# lasertag.net
KiCad netlist of a schematic drawn in EAGLE
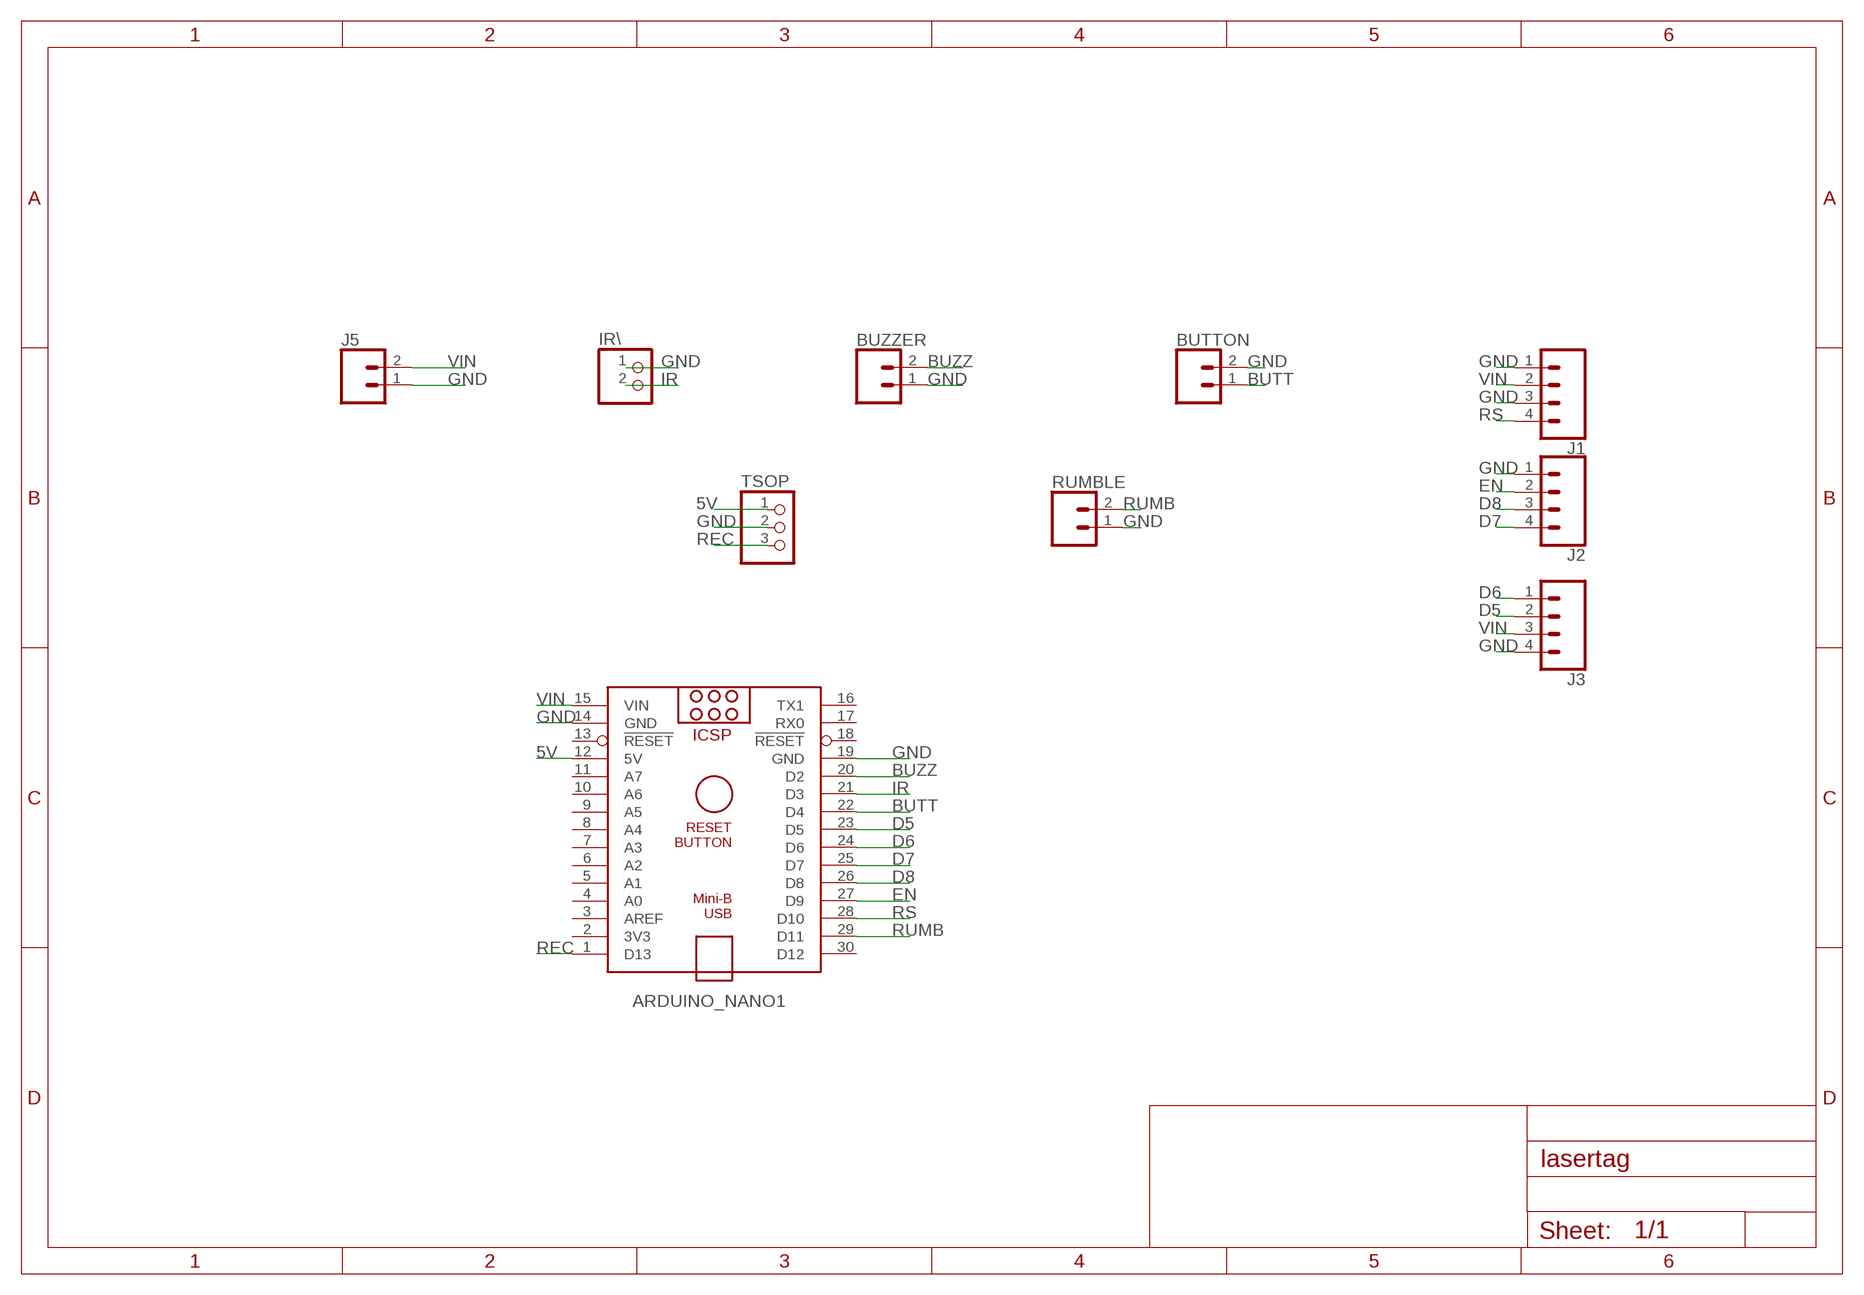
[diagram p0: schematic, sheet 1]

(export (version "E")
  (design (tool "Eeschema 10.0.6"))
  (components
    (comp (ref "ARDUINO_NANO1")
      (value "ARDUINO_NANO")
      (footprint "eagle-import:ARDUINO_NANO")
      (libsource (lib "eagle-import") (part "ARDUINO_NANO"))
    )
    (comp (ref "BUTTON")
      (value "CONN_02")
      (footprint "eagle-import:1X02")
      (libsource (lib "eagle-import") (part "CONN_02"))
    )
    (comp (ref "BUZZER")
      (value "CONN_02")
      (footprint "eagle-import:1X02")
      (libsource (lib "eagle-import") (part "CONN_02"))
    )
    (comp (ref "IR\\")
      (value "PINHD-1X2")
      (footprint "eagle-import:1X02")
      (libsource (lib "eagle-import") (part "PINHD-1X2"))
    )
    (comp (ref "J1")
      (value "CONN_04JST-PTH-VERT")
      (footprint "eagle-import:JST-4-PTH-VERT")
      (libsource (lib "eagle-import") (part "CONN_04JST-PTH-VERT"))
    )
    (comp (ref "J2")
      (value "CONN_04JST-PTH-VERT")
      (footprint "eagle-import:JST-4-PTH-VERT")
      (libsource (lib "eagle-import") (part "CONN_04JST-PTH-VERT"))
    )
    (comp (ref "J3")
      (value "CONN_04JST-PTH-VERT")
      (footprint "eagle-import:JST-4-PTH-VERT")
      (libsource (lib "eagle-import") (part "CONN_04JST-PTH-VERT"))
    )
    (comp (ref "J5")
      (value "CONN_02JST-PTH-VERT")
      (footprint "eagle-import:JST-2-PTH-VERT")
      (libsource (lib "eagle-import") (part "CONN_02JST-PTH-VERT"))
    )
    (comp (ref "RUMBLE")
      (value "CONN_02")
      (footprint "eagle-import:1X02")
      (libsource (lib "eagle-import") (part "CONN_02"))
    )
    (comp (ref "TSOP")
      (value "PINHD-1X3")
      (footprint "eagle-import:1X03")
      (libsource (lib "eagle-import") (part "PINHD-1X3"))
    )
  )
  (nets
    (net (code "1") (name "/5V") (class "Default")
      (node (ref "ARDUINO_NANO1") (pin "12") (pinfunction "5V_12") (pintype "power_in"))
      (node (ref "TSOP") (pin "1") (pinfunction "1_1") (pintype "passive"))
    )
    (net (code "2") (name "/BUTT") (class "Default")
      (node (ref "ARDUINO_NANO1") (pin "22") (pinfunction "D4_22") (pintype "bidirectional"))
      (node (ref "BUTTON") (pin "1") (pinfunction "1_1") (pintype "passive"))
    )
    (net (code "3") (name "/BUZZ") (class "Default")
      (node (ref "ARDUINO_NANO1") (pin "20") (pinfunction "D2_20") (pintype "bidirectional"))
      (node (ref "BUZZER") (pin "2") (pinfunction "2_2") (pintype "passive"))
    )
    (net (code "4") (name "/D5") (class "Default")
      (node (ref "ARDUINO_NANO1") (pin "23") (pinfunction "D5_23") (pintype "bidirectional"))
      (node (ref "J3") (pin "2") (pinfunction "2_2") (pintype "passive"))
    )
    (net (code "5") (name "/D6") (class "Default")
      (node (ref "ARDUINO_NANO1") (pin "24") (pinfunction "D6_24") (pintype "bidirectional"))
      (node (ref "J3") (pin "1") (pinfunction "1_1") (pintype "passive"))
    )
    (net (code "6") (name "/D7") (class "Default")
      (node (ref "ARDUINO_NANO1") (pin "25") (pinfunction "D7_25") (pintype "bidirectional"))
      (node (ref "J2") (pin "4") (pinfunction "4_4") (pintype "passive"))
    )
    (net (code "7") (name "/D8") (class "Default")
      (node (ref "ARDUINO_NANO1") (pin "26") (pinfunction "D8_26") (pintype "bidirectional"))
      (node (ref "J2") (pin "3") (pinfunction "3_3") (pintype "passive"))
    )
    (net (code "8") (name "/EN") (class "Default")
      (node (ref "ARDUINO_NANO1") (pin "27") (pinfunction "D9_27") (pintype "bidirectional"))
      (node (ref "J2") (pin "2") (pinfunction "2_2") (pintype "passive"))
    )
    (net (code "9") (name "/GND") (class "Default")
      (node (ref "ARDUINO_NANO1") (pin "14") (pinfunction "GND_14") (pintype "power_in"))
      (node (ref "ARDUINO_NANO1") (pin "19") (pinfunction "GND_19") (pintype "power_in"))
      (node (ref "BUTTON") (pin "2") (pinfunction "2_2") (pintype "passive"))
      (node (ref "BUZZER") (pin "1") (pinfunction "1_1") (pintype "passive"))
      (node (ref "IR\\") (pin "1") (pinfunction "1_1") (pintype "passive"))
      (node (ref "J1") (pin "1") (pinfunction "1_1") (pintype "passive"))
      (node (ref "J1") (pin "3") (pinfunction "3_3") (pintype "passive"))
      (node (ref "J2") (pin "1") (pinfunction "1_1") (pintype "passive"))
      (node (ref "J3") (pin "4") (pinfunction "4_4") (pintype "passive"))
      (node (ref "J5") (pin "1") (pinfunction "1_1") (pintype "passive"))
      (node (ref "RUMBLE") (pin "1") (pinfunction "1_1") (pintype "passive"))
      (node (ref "TSOP") (pin "2") (pinfunction "2_2") (pintype "passive"))
    )
    (net (code "10") (name "/IR") (class "Default")
      (node (ref "ARDUINO_NANO1") (pin "21") (pinfunction "D3_21") (pintype "bidirectional"))
      (node (ref "IR\\") (pin "2") (pinfunction "2_2") (pintype "passive"))
    )
    (net (code "11") (name "/REC") (class "Default")
      (node (ref "ARDUINO_NANO1") (pin "1") (pinfunction "D13_1") (pintype "bidirectional"))
      (node (ref "TSOP") (pin "3") (pinfunction "3_3") (pintype "passive"))
    )
    (net (code "12") (name "/RS") (class "Default")
      (node (ref "ARDUINO_NANO1") (pin "28") (pinfunction "D10_28") (pintype "bidirectional"))
      (node (ref "J1") (pin "4") (pinfunction "4_4") (pintype "passive"))
    )
    (net (code "13") (name "/RUMB") (class "Default")
      (node (ref "ARDUINO_NANO1") (pin "29") (pinfunction "D11_29") (pintype "bidirectional"))
      (node (ref "RUMBLE") (pin "2") (pinfunction "2_2") (pintype "passive"))
    )
    (net (code "14") (name "/VIN") (class "Default")
      (node (ref "ARDUINO_NANO1") (pin "15") (pinfunction "VIN_15") (pintype "power_in"))
      (node (ref "J1") (pin "2") (pinfunction "2_2") (pintype "passive"))
      (node (ref "J3") (pin "3") (pinfunction "3_3") (pintype "passive"))
      (node (ref "J5") (pin "2") (pinfunction "2_2") (pintype "passive"))
    )
    (net (code "15") (name "unconnected-(ARDUINO_NANO1-3V3-Pad2)") (class "Default")
      (node (ref "ARDUINO_NANO1") (pin "2") (pinfunction "3V3_2") (pintype "output"))
    )
    (net (code "16") (name "unconnected-(ARDUINO_NANO1-A0-Pad4)") (class "Default")
      (node (ref "ARDUINO_NANO1") (pin "4") (pinfunction "A0_4") (pintype "bidirectional"))
    )
    (net (code "17") (name "unconnected-(ARDUINO_NANO1-A1-Pad5)") (class "Default")
      (node (ref "ARDUINO_NANO1") (pin "5") (pinfunction "A1_5") (pintype "bidirectional"))
    )
    (net (code "18") (name "unconnected-(ARDUINO_NANO1-A2-Pad6)") (class "Default")
      (node (ref "ARDUINO_NANO1") (pin "6") (pinfunction "A2_6") (pintype "bidirectional"))
    )
    (net (code "19") (name "unconnected-(ARDUINO_NANO1-A3-Pad7)") (class "Default")
      (node (ref "ARDUINO_NANO1") (pin "7") (pinfunction "A3_7") (pintype "bidirectional"))
    )
    (net (code "20") (name "unconnected-(ARDUINO_NANO1-A4-Pad8)") (class "Default")
      (node (ref "ARDUINO_NANO1") (pin "8") (pinfunction "A4_8") (pintype "bidirectional"))
    )
    (net (code "21") (name "unconnected-(ARDUINO_NANO1-A5-Pad9)") (class "Default")
      (node (ref "ARDUINO_NANO1") (pin "9") (pinfunction "A5_9") (pintype "bidirectional"))
    )
    (net (code "22") (name "unconnected-(ARDUINO_NANO1-A6-Pad10)") (class "Default")
      (node (ref "ARDUINO_NANO1") (pin "10") (pinfunction "A6_10") (pintype "bidirectional"))
    )
    (net (code "23") (name "unconnected-(ARDUINO_NANO1-A7-Pad11)") (class "Default")
      (node (ref "ARDUINO_NANO1") (pin "11") (pinfunction "A7_11") (pintype "bidirectional"))
    )
    (net (code "24") (name "unconnected-(ARDUINO_NANO1-AREF-Pad3)") (class "Default")
      (node (ref "ARDUINO_NANO1") (pin "3") (pinfunction "AREF_3") (pintype "input"))
    )
    (net (code "25") (name "unconnected-(ARDUINO_NANO1-D12-Pad30)") (class "Default")
      (node (ref "ARDUINO_NANO1") (pin "30") (pinfunction "D12_30") (pintype "bidirectional"))
    )
    (net (code "26") (name "unconnected-(ARDUINO_NANO1-RX0-Pad17)") (class "Default")
      (node (ref "ARDUINO_NANO1") (pin "17") (pinfunction "RX0_17") (pintype "bidirectional"))
    )
    (net (code "27") (name "unconnected-(ARDUINO_NANO1-TX1-Pad16)") (class "Default")
      (node (ref "ARDUINO_NANO1") (pin "16") (pinfunction "TX1_16") (pintype "bidirectional"))
    )
    (net (code "28") (name "unconnected-(ARDUINO_NANO1-~{RESET}-Pad13)") (class "Default")
      (node (ref "ARDUINO_NANO1") (pin "13") (pinfunction "~{RESET}_13") (pintype "input"))
    )
    (net (code "29") (name "unconnected-(ARDUINO_NANO1-~{RESET}-Pad18)") (class "Default")
      (node (ref "ARDUINO_NANO1") (pin "18") (pinfunction "~{RESET}_18") (pintype "input"))
    )
  )
)
